# Main.net
KiCad netlist of a schematic drawn in Altium Designer
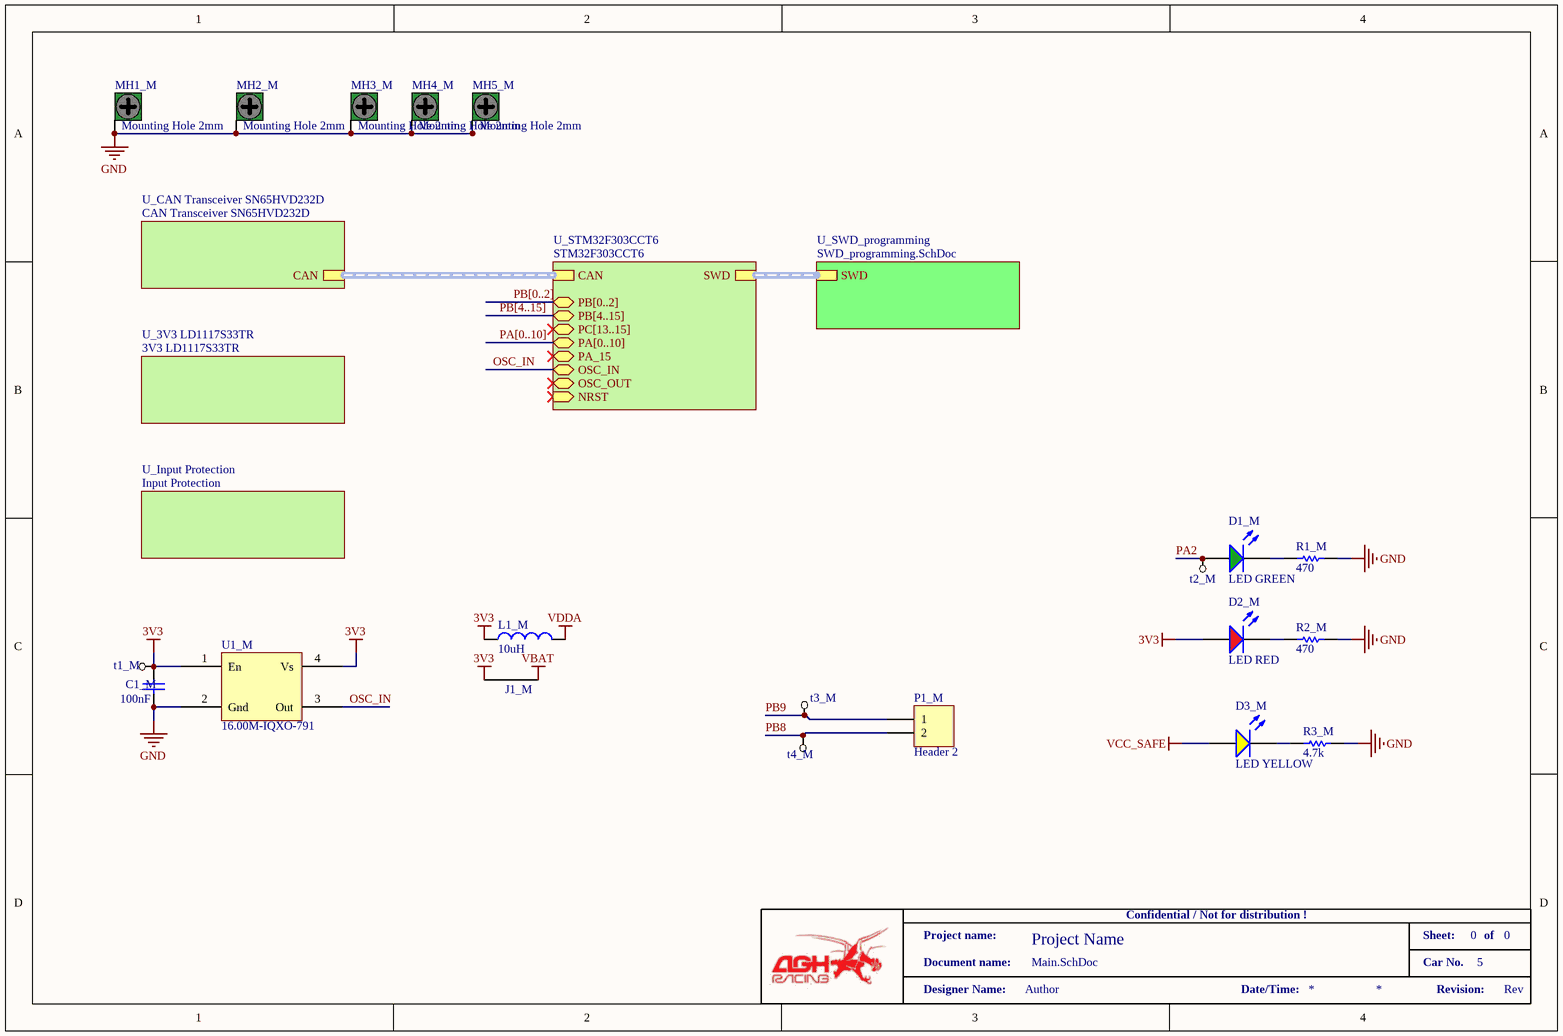
[diagram p0: Main.SchDoc]

(export (version "E")
  (design (tool "Eeschema 10.0.6"))
  (components
    (comp (ref "C1_M")
      (value "100nF")
      (footprint "CAP_0603_IPC_MD")
      (description "Capacitor")
      (fields (field (name "Comment") "Cap"))
      (libsource (lib "agh_racing_2018") (part "Cap"))
    )
    (comp (ref "D1_M")
      (value "LED GREEN")
      (footprint "LED_0603_GREEN_IPC_MD")
      (libsource (lib "agh_racing_2018") (part "LED GREEN"))
    )
    (comp (ref "D2_M")
      (value "LED RED")
      (footprint "LED_0603_RED_IPC_MD")
      (libsource (lib "agh_racing_2018") (part "LED RED"))
    )
    (comp (ref "D3_M")
      (value "LED YELLOW")
      (footprint "LED_0603_YELLOW_IPC_MD")
      (libsource (lib "agh_racing_2018") (part "LED YELLOW"))
    )
    (comp (ref "J1_M")
      (value "NetTie")
      (footprint "NETTIE")
      (libsource (lib "agh_racing_2018") (part "NetTie"))
    )
    (comp (ref "L1_M")
      (value "10uH")
      (footprint "IND_0603_IPC_HD")
      (description "Inductor")
      (fields (field (name "Comment") "Ind"))
      (libsource (lib "agh_racing_2018") (part "Ind"))
    )
    (comp (ref "MH1_M")
      (value "Mounting Hole 2mm")
      (footprint "MOUNTING HOLE 3mm")
      (libsource (lib "agh_racing_2018") (part "Mounting Hole"))
    )
    (comp (ref "MH2_M")
      (value "Mounting Hole 2mm")
      (footprint "MOUNTING HOLE 3mm")
      (libsource (lib "agh_racing_2018") (part "Mounting Hole"))
    )
    (comp (ref "MH3_M")
      (value "Mounting Hole 2mm")
      (footprint "MOUNTING HOLE 3mm")
      (libsource (lib "agh_racing_2018") (part "Mounting Hole"))
    )
    (comp (ref "MH4_M")
      (value "Mounting Hole 2mm")
      (footprint "MOUNTING HOLE 3mm")
      (libsource (lib "agh_racing_2018") (part "Mounting Hole"))
    )
    (comp (ref "MH5_M")
      (value "Mounting Hole 2mm")
      (footprint "MOUNTING HOLE 3mm")
      (libsource (lib "agh_racing_2018") (part "Mounting Hole"))
    )
    (comp (ref "P1_M")
      (value "Header 2")
      (footprint "MOLEX_2PIN")
      (description "Header, 2-Pin")
      (libsource (lib "agh_racing_2018") (part "Header 2"))
    )
    (comp (ref "R1_M")
      (value "470")
      (footprint "RES_0603_IPC_MD")
      (description "Resistor")
      (fields (field (name "Comment") "Res"))
      (libsource (lib "agh_racing_2018") (part "Res"))
    )
    (comp (ref "R2_M")
      (value "470")
      (footprint "RES_0603_IPC_MD")
      (description "Resistor")
      (fields (field (name "Comment") "Res"))
      (libsource (lib "agh_racing_2018") (part "Res"))
    )
    (comp (ref "R3_M")
      (value "4.7k")
      (footprint "RES_0603_IPC_MD")
      (description "Resistor")
      (fields (field (name "Comment") "Res"))
      (libsource (lib "agh_racing_2018") (part "Res"))
    )
    (comp (ref "t1_M")
      (value "Test point")
      (footprint "Via_Test_Point")
      (libsource (lib "agh_racing_2019") (part "Test Point"))
    )
    (comp (ref "t2_M")
      (value "Test point")
      (footprint "Via_Test_Point")
      (libsource (lib "agh_racing_2019") (part "Test Point"))
    )
    (comp (ref "t3_M")
      (value "Test point")
      (footprint "Via_Test_Point")
      (libsource (lib "agh_racing_2019") (part "Test Point"))
    )
    (comp (ref "t4_M")
      (value "Test point")
      (footprint "Via_Test_Point")
      (libsource (lib "agh_racing_2019") (part "Test Point"))
    )
    (comp (ref "U1_M")
      (value "16.00M-IQXO-791")
      (footprint "ICLCX18")
      (description "Crystal Clock Oscillator")
      (fields
        (field (name "MANUFACTURER") "IQD FREQUENCY PRODUCTS")
        (field (name "MPN") "LFSPXO066657CUTT")
        (field (name "NAME") "16.00M-IQXO-791")
      )
      (libsource (lib "agh_racing_2018_temp") (part "16.00M-IQXO-791"))
    )
  )
  (nets
    (net (code "26") (name "/OSC_IN") (class "Default")
      (node (ref "U1_M") (pin "3") (pinfunction "Out_3") (pintype "passive"))
    )
    (net (code "28") (name "/PA2") (class "Default")
      (node (ref "D1_M") (pin "1") (pinfunction "A_1") (pintype "passive"))
      (node (ref "t2_M") (pin "1") (pinfunction "1_1") (pintype "open_collector"))
    )
    (net (code "31") (name "/PB8") (class "Default")
      (node (ref "P1_M") (pin "2") (pinfunction "2_2") (pintype "passive"))
      (node (ref "t4_M") (pin "1") (pinfunction "1_1") (pintype "open_collector"))
    )
    (net (code "32") (name "/PB9") (class "Default")
      (node (ref "P1_M") (pin "1") (pinfunction "1_1") (pintype "passive"))
      (node (ref "t3_M") (pin "1") (pinfunction "1_1") (pintype "open_collector"))
    )
    (net (code "37") (name "3V3") (class "Default")
      (node (ref "C1_M") (pin "2") (pinfunction "2_2") (pintype "passive"))
      (node (ref "D2_M") (pin "1") (pinfunction "A_1") (pintype "passive"))
      (node (ref "J1_M") (pin "1") (pinfunction "1_1") (pintype "passive"))
      (node (ref "L1_M") (pin "1") (pinfunction "1_1") (pintype "passive"))
      (node (ref "U1_M") (pin "1") (pinfunction "En_1") (pintype "passive"))
      (node (ref "U1_M") (pin "4") (pinfunction "Vs_4") (pintype "passive"))
    )
    (net (code "38") (name "GND") (class "Default")
      (node (ref "C1_M") (pin "1") (pinfunction "1_1") (pintype "passive"))
      (node (ref "MH1_M") (pin "MOUNTING") (pinfunction "MOUNTING_MOUNTING") (pintype "passive"))
      (node (ref "MH2_M") (pin "MOUNTING") (pinfunction "MOUNTING_MOUNTING") (pintype "passive"))
      (node (ref "MH3_M") (pin "MOUNTING") (pinfunction "MOUNTING_MOUNTING") (pintype "passive"))
      (node (ref "MH4_M") (pin "MOUNTING") (pinfunction "MOUNTING_MOUNTING") (pintype "passive"))
      (node (ref "MH5_M") (pin "MOUNTING") (pinfunction "MOUNTING_MOUNTING") (pintype "passive"))
      (node (ref "R1_M") (pin "1") (pinfunction "1_1") (pintype "passive"))
      (node (ref "R2_M") (pin "1") (pinfunction "1_1") (pintype "passive"))
      (node (ref "R3_M") (pin "1") (pinfunction "1_1") (pintype "passive"))
      (node (ref "U1_M") (pin "2") (pinfunction "Gnd_2") (pintype "passive"))
    )
    (net (code "39") (name "Net-(D1_M-K)") (class "Default")
      (node (ref "D1_M") (pin "2") (pinfunction "K_2") (pintype "passive"))
      (node (ref "R1_M") (pin "2") (pinfunction "2_2") (pintype "passive"))
    )
    (net (code "40") (name "Net-(D2_M-K)") (class "Default")
      (node (ref "D2_M") (pin "2") (pinfunction "K_2") (pintype "passive"))
      (node (ref "R2_M") (pin "2") (pinfunction "2_2") (pintype "passive"))
    )
    (net (code "41") (name "Net-(D3_M-K)") (class "Default")
      (node (ref "D3_M") (pin "2") (pinfunction "K_2") (pintype "passive"))
      (node (ref "R3_M") (pin "2") (pinfunction "2_2") (pintype "passive"))
    )
    (net (code "42") (name "VBAT") (class "Default")
      (node (ref "J1_M") (pin "2") (pinfunction "2_2") (pintype "passive"))
    )
    (net (code "43") (name "VCC_SAFE") (class "Default")
      (node (ref "D3_M") (pin "1") (pinfunction "A_1") (pintype "passive"))
    )
    (net (code "44") (name "VDDA") (class "Default")
      (node (ref "L1_M") (pin "2") (pinfunction "2_2") (pintype "passive"))
    )
    (net (code "45") (name "unconnected-(t1_M-Pad1)") (class "Default")
      (node (ref "t1_M") (pin "1") (pinfunction "1_1") (pintype "open_collector"))
    )
  )
)
